# MAIN-BRUSH-MOTOR.net
KiCad netlist of a schematic drawn in Altium Designer
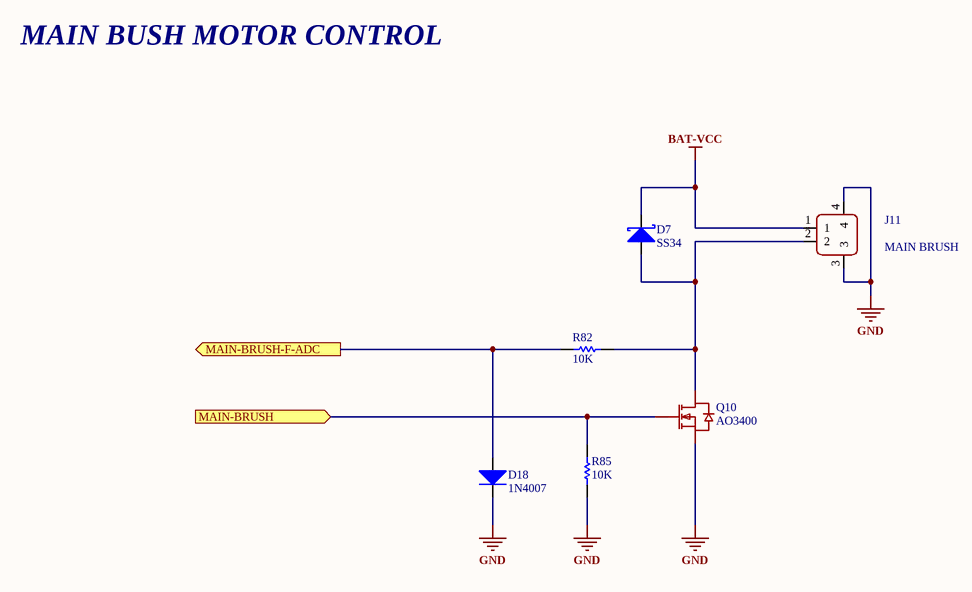
[diagram p0: MAIN-BRUSH-MOTOR .SchDoc]

(export (version "E")
  (design (tool "Eeschema 10.0.6"))
  (components
    (comp (ref "D7") (value "SS34") (footprint "SMA") (libsource (lib "DesignLibrary") (part "DIODE-2")))
    (comp (ref "D18")
      (value "1N4007")
      (footprint "SOD123")
      (libsource (lib "DesignLibrary") (part "DIODE-1"))
    )
    (comp (ref "J11")
      (value "MAIN BRUSH")
      (footprint "CONN-SMD_2P-P2.00_XUNPU_WAFER-PH2.0-2PWB")
      (description "ZX-ZH1.5-2PWT")
      (libsource (lib "DesignLibrary") (part "HDRx2"))
    )
    (comp (ref "Q10")
      (value "AO3400")
      (footprint "SOT23-3D")
      (libsource (lib "DesignLibrary") (part "N-MOS-SOT23"))
    )
    (comp (ref "R82")
      (value "10K")
      (footprint "RES-0402")
      (libsource (lib "DesignLibrary") (part "Resistor-1"))
    )
    (comp (ref "R85")
      (value "10K")
      (footprint "RES-0402")
      (libsource (lib "DesignLibrary") (part "Resistor-1"))
    )
  )
  (nets
    (net (code "1") (name "/MAIN-BRUSH") (class "Default")
      (node (ref "Q10") (pin "1") (pinfunction "G_1") (pintype "passive"))
      (node (ref "R85") (pin "1") (pintype "passive"))
    )
    (net (code "2") (name "/MAIN-BRUSH-F-ADC") (class "Default")
      (node (ref "D18") (pin "1") (pinfunction "A_1") (pintype "passive"))
      (node (ref "R82") (pin "1") (pintype "passive"))
    )
    (net (code "3") (name "BAT-VCC") (class "Default")
      (node (ref "D7") (pin "2") (pinfunction "K_2") (pintype "passive"))
      (node (ref "J11") (pin "1") (pinfunction "1_1") (pintype "passive"))
    )
    (net (code "4") (name "GND") (class "Default")
      (node (ref "D18") (pin "2") (pinfunction "K_2") (pintype "passive"))
      (node (ref "J11") (pin "3") (pinfunction "3_3") (pintype "passive"))
      (node (ref "J11") (pin "4") (pinfunction "4_4") (pintype "passive"))
      (node (ref "Q10") (pin "2") (pinfunction "S_2") (pintype "passive"))
      (node (ref "R85") (pin "2") (pintype "passive"))
    )
    (net (code "5") (name "Net-(D7-A)") (class "Default")
      (node (ref "D7") (pin "1") (pinfunction "A_1") (pintype "passive"))
      (node (ref "J11") (pin "2") (pinfunction "2_2") (pintype "passive"))
      (node (ref "Q10") (pin "3") (pinfunction "D_3") (pintype "passive"))
      (node (ref "R82") (pin "2") (pintype "passive"))
    )
  )
)
